# Air_SCH.net
KiCad netlist of a schematic drawn in Altium Designer
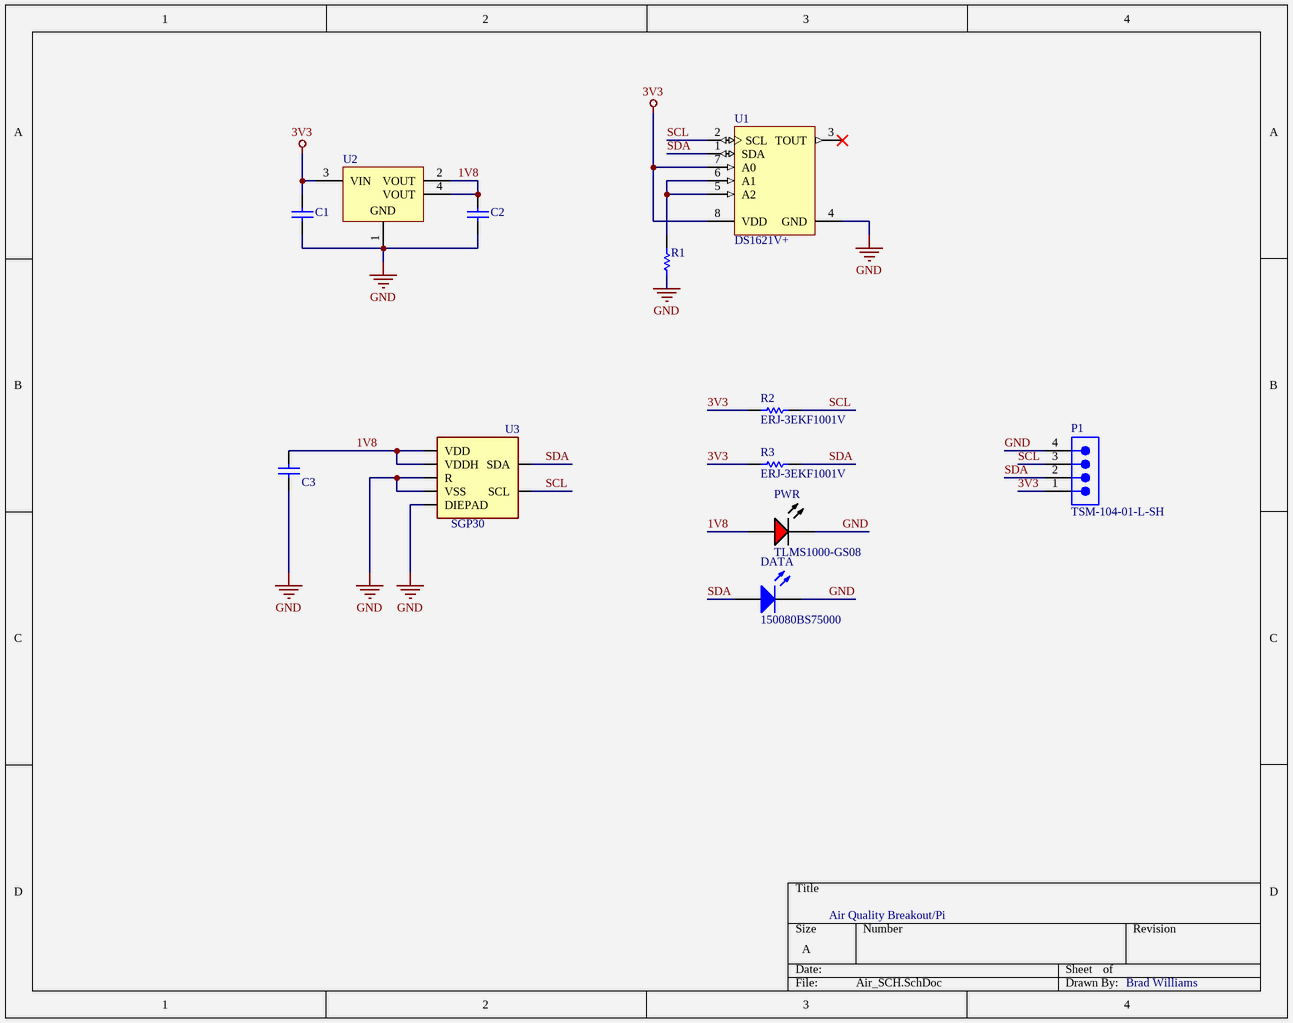
[diagram p0: Air_SCH.SchDoc]

(export (version "E")
  (design (tool "Eeschema 10.0.6"))
  (components
    (comp (ref "C1")
      (value "CGA3E2X7R1H104K080AA")
      (footprint "CAPC1608X90X20LL10")
      (description "Chip Capacitor, 0.1 uF, +/- 10%, 50 V, -55 to 125 degC, 0603 (1608 Metric), RoHS, Tape and Reel")
      (fields (field (name "VOLTAGE") "50V") (field (name "TOLERANCE") "10%"))
      (libsource (lib "Altium Content Vault") (part "CAP-NP-2"))
    )
    (comp (ref "C2")
      (value "GCM21BR70J106KE22L")
      (footprint "CAPC2013X140X45LL15T25")
      (fields (field (name "MANUFACTURER") "Murata"))
      (libsource (lib "Altium Content Vault") (part "CAP"))
    )
    (comp (ref "C3")
      (value "CGA3E2X7R1H104K080AA")
      (footprint "CAPC1608X90X20LL10")
      (description "Chip Capacitor, 0.1 uF, +/- 10%, 50 V, -55 to 125 degC, 0603 (1608 Metric), RoHS, Tape and Reel")
      (fields (field (name "VOLTAGE") "50V") (field (name "TOLERANCE") "10%"))
      (libsource (lib "Altium Content Vault") (part "CAP-NP-2"))
    )
    (comp (ref "DATA")
      (value "150080BS75000")
      (footprint "0805_A")
      (description "SMD mono-color Chip LED, WL-SMCW, Blue")
      (fields (field (name "MANUFACTURER") "Wuerth Elektronik"))
      (libsource (lib "Altium Content Vault") (part "WE-LED_K1A2-2"))
    )
    (comp (ref "P1")
      (value "TSM-104-01-L-SH")
      (footprint "SMTC-TSM-104-01-X-SH")
      (fields (field (name "MANUFACTURER") "Samtec"))
      (libsource (lib "Altium Content Vault") (part "SMTC-TSM-104-01-X-SH"))
    )
    (comp (ref "PWR")
      (value "TLMS1000-GS08")
      (footprint "VISH-TLMS1000_V")
      (description "Low Current LED, 40 mW, 1.8 V, -40 to 100 degC, 2-Pin SMD (0603), RoHS, Tape and Reel")
      (fields (field (name "MANUFACTURER") "Vishay"))
      (libsource (lib "Altium Content Vault") (part "LED-RED-AK-2"))
    )
    (comp (ref "R1")
      (value "ERJ3EKF1002V")
      (footprint "RESC1609X55X30LL15T15")
      (description "Chip Resistor, 10 KOhm, +/- 1%, 0.1 W, -55 to 155 degC, 0603 (1608 Metric), RoHS, Tape and Reel")
      (fields (field (name "TOLERANCE") "1%") (field (name "MANUFACTURER") "Panasonic"))
      (libsource (lib "Altium Content Vault") (part "RES-2"))
    )
    (comp (ref "R2")
      (value "ERJ-3EKF1001V")
      (footprint "RESC1608X55X30LL15T15")
      (fields (field (name "MANUFACTURER") "Panasonic"))
      (libsource (lib "Altium Content Vault") (part "RES"))
    )
    (comp (ref "R3")
      (value "ERJ-3EKF1001V")
      (footprint "RESC1608X55X30LL15T15")
      (fields (field (name "MANUFACTURER") "Panasonic"))
      (libsource (lib "Altium Content Vault") (part "RES"))
    )
    (comp (ref "U1")
      (value "DS1621V+")
      (footprint "MAXM-W8+2_L")
      (fields (field (name "GENERIC PART NUMBER") "DS1621"))
      (libsource (lib "Altium Content Vault") (part "DS1X21-X8XX"))
    )
    (comp (ref "U2")
      (value "LD1117AS18TR")
      (footprint "SOT-223_L")
      (description "1A, Low Drop Positive Voltage Regulator, 1.8V, 4-Pin SOT-223, Tape and Reel")
      (libsource (lib "Altium Content Vault") (part "PM-REG-LD1117-SOT4"))
    )
    (comp (ref "U3")
      (value "SGP30")
      (footprint "SGP30")
      (description "AIR QUALITY GAS SENSOR FOR VOC'S")
      (fields (field (name "MF") "Sensirion AG"))
      (libsource (lib "Brad Williams") (part "SGP30"))
    )
  )
  (nets
    (net (code "1") (name "/1V8") (class "Default")
      (node (ref "C2") (pin "2") (pinfunction "2_2") (pintype "passive"))
      (node (ref "C3") (pin "2") (pinfunction "2_2") (pintype "passive"))
      (node (ref "PWR") (pin "1") (pinfunction "A_1") (pintype "passive"))
      (node (ref "U2") (pin "2") (pinfunction "VOUT_2") (pintype "power_in"))
      (node (ref "U2") (pin "4") (pinfunction "VOUT_4") (pintype "power_in"))
      (node (ref "U3") (pin "1") (pinfunction "VDD_1") (pintype "bidirectional"))
      (node (ref "U3") (pin "5") (pinfunction "VDDH_5") (pintype "bidirectional"))
    )
    (net (code "2") (name "/SCL") (class "Default")
      (node (ref "P1") (pin "3") (pinfunction "3_3") (pintype "passive"))
      (node (ref "R2") (pin "2") (pinfunction "2_2") (pintype "passive"))
      (node (ref "U1") (pin "2") (pinfunction "SCL_2") (pintype "bidirectional"))
      (node (ref "U3") (pin "6") (pinfunction "SCL_6") (pintype "bidirectional"))
    )
    (net (code "3") (name "/SDA") (class "Default")
      (node (ref "DATA") (pin "2") (pinfunction "A_2") (pintype "passive"))
      (node (ref "P1") (pin "2") (pinfunction "2_2") (pintype "passive"))
      (node (ref "R3") (pin "2") (pinfunction "2_2") (pintype "passive"))
      (node (ref "U1") (pin "1") (pinfunction "SDA_1") (pintype "bidirectional"))
      (node (ref "U3") (pin "3") (pinfunction "SDA_3") (pintype "bidirectional"))
    )
    (net (code "4") (name "3V3") (class "Default")
      (node (ref "C1") (pin "2") (pinfunction "2_2") (pintype "passive"))
      (node (ref "P1") (pin "1") (pinfunction "1_1") (pintype "passive"))
      (node (ref "R2") (pin "1") (pinfunction "1_1") (pintype "passive"))
      (node (ref "R3") (pin "1") (pinfunction "1_1") (pintype "passive"))
      (node (ref "U1") (pin "7") (pinfunction "A0_7") (pintype "input"))
      (node (ref "U1") (pin "8") (pinfunction "VDD_8") (pintype "power_in"))
      (node (ref "U2") (pin "3") (pinfunction "VIN_3") (pintype "power_in"))
    )
    (net (code "5") (name "GND") (class "Default")
      (node (ref "C1") (pin "1") (pinfunction "1_1") (pintype "passive"))
      (node (ref "C2") (pin "1") (pinfunction "1_1") (pintype "passive"))
      (node (ref "C3") (pin "1") (pinfunction "1_1") (pintype "passive"))
      (node (ref "DATA") (pin "1") (pinfunction "K_1") (pintype "passive"))
      (node (ref "P1") (pin "4") (pinfunction "4_4") (pintype "passive"))
      (node (ref "PWR") (pin "2") (pinfunction "K_2") (pintype "passive"))
      (node (ref "R1") (pin "2") (pinfunction "2_2") (pintype "passive"))
      (node (ref "U1") (pin "4") (pinfunction "GND_4") (pintype "power_in"))
      (node (ref "U2") (pin "1") (pinfunction "GND_1") (pintype "power_in"))
      (node (ref "U3") (pin "2") (pinfunction "VSS_2") (pintype "bidirectional"))
      (node (ref "U3") (pin "4") (pinfunction "R_4") (pintype "bidirectional"))
      (node (ref "U3") (pin "DIEPAD") (pinfunction "DIEPAD_DIEPAD") (pintype "bidirectional"))
    )
    (net (code "6") (name "Net-(U1-A1)") (class "Default")
      (node (ref "R1") (pin "1") (pinfunction "1_1") (pintype "passive"))
      (node (ref "U1") (pin "5") (pinfunction "A2_5") (pintype "input"))
      (node (ref "U1") (pin "6") (pinfunction "A1_6") (pintype "input"))
    )
    (net (code "7") (name "unconnected-(U1-TOUT-Pad3)") (class "Default")
      (node (ref "U1") (pin "3") (pinfunction "TOUT_3") (pintype "output+no_connect"))
    )
  )
)
